# ControlBrick2_0.net
KiCad netlist of a schematic drawn in Altium Designer
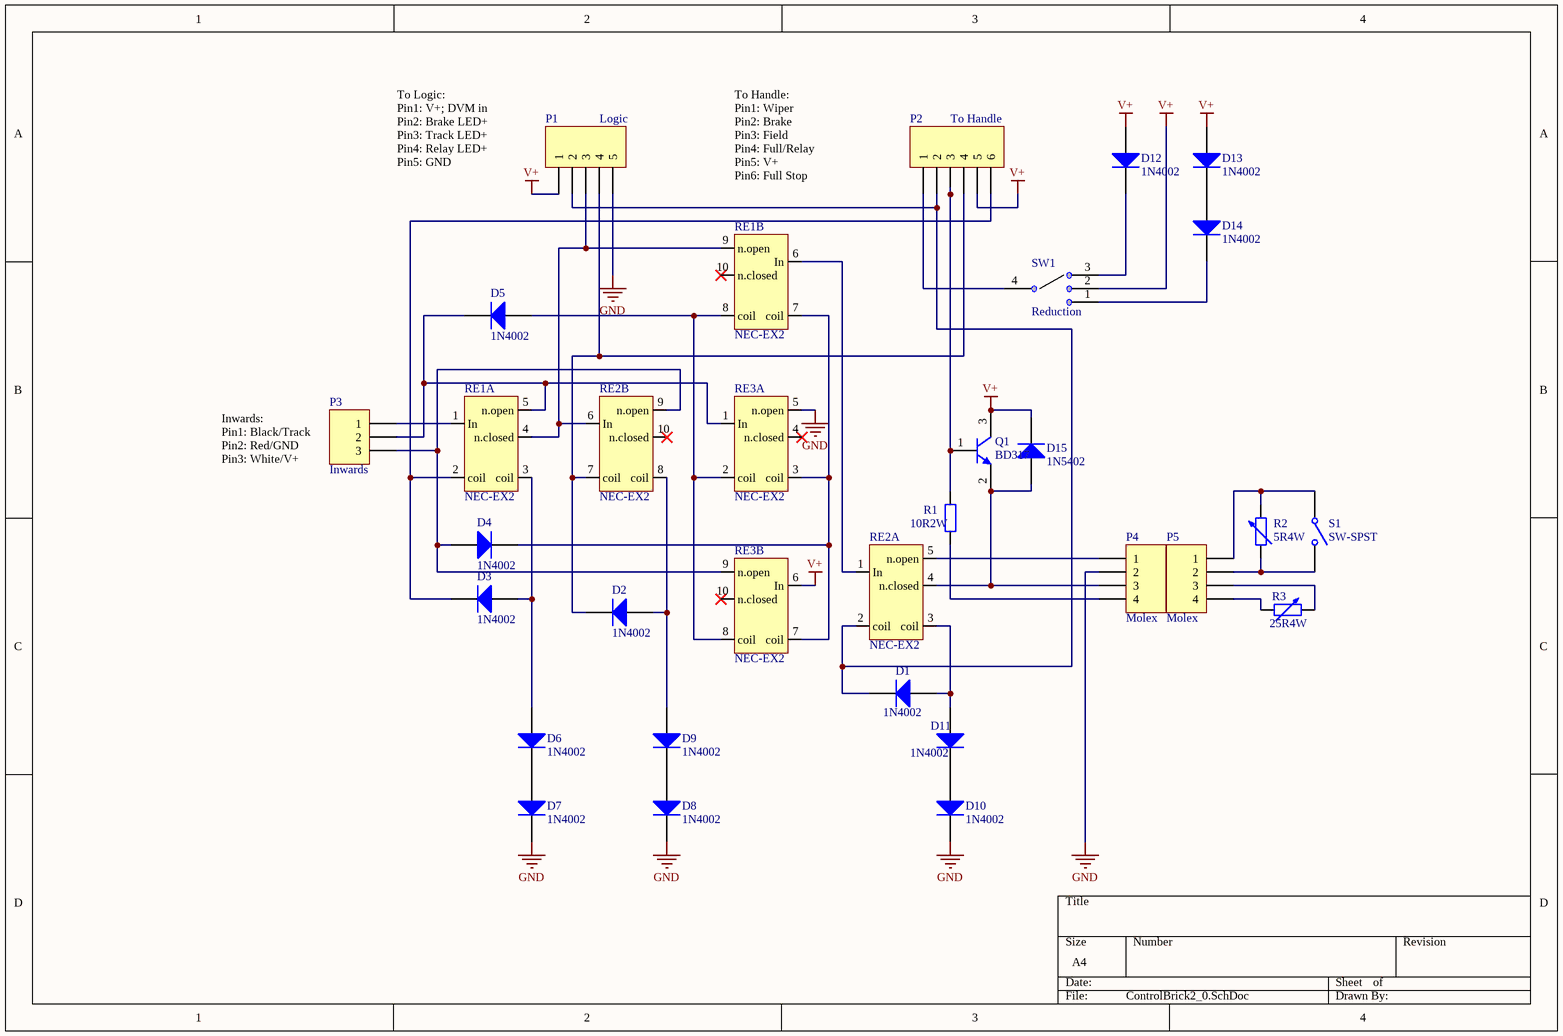
[diagram p0: ControlBrick2_0.SchDoc]

(export (version "E")
  (design (tool "Eeschema 10.0.6"))
  (components
    (comp (ref "D1")
      (value "1N4002")
      (footprint "StdDiode")
      (description "1 Amp General Purpose Rectifier")
      (fields (field (name "PUBLISHER") "Altium Limited"))
      (libsource (lib "Miscellaneous Devices") (part "Diode 1N4002"))
    )
    (comp (ref "D2")
      (value "1N4002")
      (footprint "StdDiode")
      (description "1 Amp General Purpose Rectifier")
      (fields (field (name "PUBLISHER") "Altium Limited"))
      (libsource (lib "Miscellaneous Devices") (part "Diode 1N4002"))
    )
    (comp (ref "D3")
      (value "1N4002")
      (footprint "StdDiode")
      (description "1 Amp General Purpose Rectifier")
      (fields (field (name "PUBLISHER") "Altium Limited"))
      (libsource (lib "Miscellaneous Devices") (part "Diode 1N4002"))
    )
    (comp (ref "D4")
      (value "1N4002")
      (footprint "StdDiode")
      (description "1 Amp General Purpose Rectifier")
      (fields (field (name "PUBLISHER") "Altium Limited"))
      (libsource (lib "Miscellaneous Devices") (part "Diode 1N4002"))
    )
    (comp (ref "D5")
      (value "1N4002")
      (footprint "StdDiode")
      (description "1 Amp General Purpose Rectifier")
      (fields (field (name "PUBLISHER") "Altium Limited"))
      (libsource (lib "Miscellaneous Devices") (part "Diode 1N4002"))
    )
    (comp (ref "D6")
      (value "1N4002")
      (footprint "StdDiode")
      (description "1 Amp General Purpose Rectifier")
      (fields (field (name "PUBLISHER") "Altium Limited"))
      (libsource (lib "Miscellaneous Devices") (part "Diode 1N4002"))
    )
    (comp (ref "D7")
      (value "1N4002")
      (footprint "StdDiode")
      (description "1 Amp General Purpose Rectifier")
      (fields (field (name "PUBLISHER") "Altium Limited"))
      (libsource (lib "Miscellaneous Devices") (part "Diode 1N4002"))
    )
    (comp (ref "D8")
      (value "1N4002")
      (footprint "StdDiode")
      (description "1 Amp General Purpose Rectifier")
      (fields (field (name "PUBLISHER") "Altium Limited"))
      (libsource (lib "Miscellaneous Devices") (part "Diode 1N4002"))
    )
    (comp (ref "D9")
      (value "1N4002")
      (footprint "StdDiode")
      (description "1 Amp General Purpose Rectifier")
      (fields (field (name "PUBLISHER") "Altium Limited"))
      (libsource (lib "Miscellaneous Devices") (part "Diode 1N4002"))
    )
    (comp (ref "D10")
      (value "1N4002")
      (footprint "StdDiode")
      (description "1 Amp General Purpose Rectifier")
      (fields (field (name "PUBLISHER") "Altium Limited"))
      (libsource (lib "Miscellaneous Devices") (part "Diode 1N4002"))
    )
    (comp (ref "D11")
      (value "1N4002")
      (footprint "StdDiode")
      (description "1 Amp General Purpose Rectifier")
      (fields (field (name "PUBLISHER") "Altium Limited"))
      (libsource (lib "Miscellaneous Devices") (part "Diode 1N4002"))
    )
    (comp (ref "D12")
      (value "1N4002")
      (footprint "StdDiode")
      (description "1 Amp General Purpose Rectifier")
      (fields (field (name "PUBLISHER") "Altium Limited"))
      (libsource (lib "Miscellaneous Devices") (part "Diode 1N4002"))
    )
    (comp (ref "D13")
      (value "1N4002")
      (footprint "StdDiode")
      (description "1 Amp General Purpose Rectifier")
      (fields (field (name "PUBLISHER") "Altium Limited"))
      (libsource (lib "Miscellaneous Devices") (part "Diode 1N4002"))
    )
    (comp (ref "D14")
      (value "1N4002")
      (footprint "StdDiode")
      (description "1 Amp General Purpose Rectifier")
      (fields (field (name "PUBLISHER") "Altium Limited"))
      (libsource (lib "Miscellaneous Devices") (part "Diode 1N4002"))
    )
    (comp (ref "D15")
      (value "1N5402")
      (footprint "BigDiode")
      (description "3 Amp General Purpose Rectifier")
      (fields (field (name "PUBLISHER") "Altium Limited"))
      (libsource (lib "Miscellaneous Devices") (part "Diode 1N5402"))
    )
    (comp (ref "P1")
      (value "Logic")
      (footprint "HDR1X5")
      (description "Header, 5-Pin")
      (fields (field (name "PUBLISHER") "Altium Limited"))
      (libsource (lib "Miscellaneous Connectors") (part "Header 5"))
    )
    (comp (ref "P2")
      (value "To Handle")
      (footprint "Interconnect")
      (description "Header, 6-Pin")
      (fields (field (name "PUBLISHER") "Altium Limited"))
      (libsource (lib "Miscellaneous Connectors") (part "Header 6"))
    )
    (comp (ref "P3")
      (value "Inwards")
      (footprint "Inwards")
      (description "Header, 3-Pin")
      (fields (field (name "PUBLISHER") "Altium Limited"))
      (libsource (lib "Miscellaneous Connectors") (part "Header 3"))
    )
    (comp (ref "P4")
      (value "Molex")
      (footprint "Molex_4x50.8")
      (description "Header, 4-Pin")
      (fields (field (name "PUBLISHER") "Altium Limited"))
      (libsource (lib "Miscellaneous Connectors") (part "Header 4"))
    )
    (comp (ref "P5")
      (value "Molex")
      (footprint "HDR1X4")
      (description "Header, 4-Pin")
      (fields (field (name "PUBLISHER") "Altium Limited"))
      (libsource (lib "") (part "Header 4_1"))
    )
    (comp (ref "Q1")
      (value "BD317")
      (footprint "TO-3")
      (description "NPN General Purpose Amplifier")
      (fields (field (name "PUBLISHER") "Altium Limited"))
      (libsource (lib "Miscellaneous Devices") (part "2N3904"))
    )
    (comp (ref "R1")
      (value "10R2W")
      (footprint "2Wres")
      (description "Resistor")
      (fields (field (name "PUBLISHER") "Altium Limited"))
      (libsource (lib "Miscellaneous Devices") (part "Res2"))
    )
    (comp (ref "R2")
      (value "5R4W")
      (footprint "AXIAL-0.6")
      (description "Variable Resistor")
      (fields (field (name "Comment") "Res Adj2") (field (name "PUBLISHER") "Altium Limited"))
      (libsource (lib "") (part "Res Adj2_1"))
    )
    (comp (ref "R3")
      (value "25R4W")
      (footprint "AXIAL-0.6")
      (description "Variable Resistor")
      (fields (field (name "Comment") "Res Adj2") (field (name "PUBLISHER") "Altium Limited"))
      (libsource (lib "Miscellaneous Devices") (part "Res Adj2"))
    )
    (comp (ref "RE1") (value "NEC-EX2") (footprint "NEC-EX2") (libsource (lib "") (part "Component_2_1")))
    (comp (ref "RE2")
      (value "NEC-EX2")
      (footprint "NEC-EX2")
      (libsource (lib "Schlib2") (part "Component_2"))
    )
    (comp (ref "RE3")
      (value "NEC-EX2")
      (footprint "NEC-EX2")
      (libsource (lib "Schlib2") (part "NEC-EX2-2U1S"))
    )
    (comp (ref "S1")
      (value "SW-SPST")
      (footprint "Switch SPST")
      (description "Single-Pole, Single-Throw Switch")
      (fields (field (name "PUBLISHER") "Altium Limited"))
      (libsource (lib "Miscellaneous Devices") (part "SW-SPST"))
    )
    (comp (ref "SW1") (value "Reduction") (footprint "Switch SP3T") (libsource (lib "Schlib1") (part "3Way")))
  )
  (nets
    (net (code "1") (name "GND") (class "Default")
      (node (ref "D10") (pin "2") (pinfunction "K_2") (pintype "passive"))
      (node (ref "D7") (pin "2") (pinfunction "K_2") (pintype "passive"))
      (node (ref "D8") (pin "2") (pinfunction "K_2") (pintype "passive"))
      (node (ref "P1") (pin "5") (pinfunction "5_5") (pintype "passive"))
      (node (ref "P4") (pin "2") (pinfunction "2_2") (pintype "passive"))
      (node (ref "RE3") (pin "5") (pinfunction "n.open_5") (pintype "passive"))
    )
    (net (code "2") (name "Net-(D1-A)") (class "Default")
      (node (ref "D1") (pin "1") (pinfunction "A_1") (pintype "passive"))
      (node (ref "D11") (pin "1") (pinfunction "A_1") (pintype "passive"))
      (node (ref "RE2") (pin "3") (pinfunction "coil_3") (pintype "passive"))
    )
    (net (code "3") (name "Net-(D1-K)") (class "Default")
      (node (ref "D1") (pin "2") (pinfunction "K_2") (pintype "passive"))
      (node (ref "P1") (pin "2") (pinfunction "2_2") (pintype "passive"))
      (node (ref "P2") (pin "2") (pinfunction "2_2") (pintype "passive"))
      (node (ref "RE2") (pin "2") (pinfunction "coil_2") (pintype "passive"))
    )
    (net (code "4") (name "Net-(D2-A)") (class "Default")
      (node (ref "D2") (pin "1") (pinfunction "A_1") (pintype "passive"))
      (node (ref "D9") (pin "1") (pinfunction "A_1") (pintype "passive"))
      (node (ref "RE2") (pin "8") (pinfunction "coil_8") (pintype "passive"))
    )
    (net (code "5") (name "Net-(D2-K)") (class "Default")
      (node (ref "D2") (pin "2") (pinfunction "K_2") (pintype "passive"))
      (node (ref "P1") (pin "4") (pinfunction "4_4") (pintype "passive"))
      (node (ref "P2") (pin "4") (pinfunction "4_4") (pintype "passive"))
      (node (ref "RE2") (pin "7") (pinfunction "coil_7") (pintype "passive"))
    )
    (net (code "6") (name "Net-(D3-A)") (class "Default")
      (node (ref "D3") (pin "1") (pinfunction "A_1") (pintype "passive"))
      (node (ref "D6") (pin "1") (pinfunction "A_1") (pintype "passive"))
      (node (ref "RE1") (pin "3") (pinfunction "coil_3") (pintype "passive"))
    )
    (net (code "7") (name "Net-(D3-K)") (class "Default")
      (node (ref "D3") (pin "2") (pinfunction "K_2") (pintype "passive"))
      (node (ref "P2") (pin "6") (pinfunction "6_6") (pintype "passive"))
      (node (ref "RE1") (pin "2") (pinfunction "coil_2") (pintype "passive"))
    )
    (net (code "8") (name "Net-(D4-A)") (class "Default")
      (node (ref "D4") (pin "1") (pinfunction "A_1") (pintype "passive"))
      (node (ref "P3") (pin "3") (pinfunction "3_3") (pintype "passive"))
      (node (ref "RE2") (pin "9") (pinfunction "n.open_9") (pintype "passive"))
      (node (ref "RE3") (pin "9") (pinfunction "n.open_9") (pintype "passive"))
    )
    (net (code "9") (name "Net-(D4-K)") (class "Default")
      (node (ref "D4") (pin "2") (pinfunction "K_2") (pintype "passive"))
      (node (ref "RE1") (pin "7") (pinfunction "coil_7") (pintype "passive"))
      (node (ref "RE3") (pin "3") (pinfunction "coil_3") (pintype "passive"))
      (node (ref "RE3") (pin "7") (pinfunction "coil_7") (pintype "passive"))
    )
    (net (code "10") (name "Net-(D5-A)") (class "Default")
      (node (ref "D5") (pin "1") (pinfunction "A_1") (pintype "passive"))
      (node (ref "RE1") (pin "8") (pinfunction "coil_8") (pintype "passive"))
      (node (ref "RE3") (pin "2") (pinfunction "coil_2") (pintype "passive"))
      (node (ref "RE3") (pin "8") (pinfunction "coil_8") (pintype "passive"))
    )
    (net (code "11") (name "Net-(D5-K)") (class "Default")
      (node (ref "D5") (pin "2") (pinfunction "K_2") (pintype "passive"))
      (node (ref "P3") (pin "2") (pinfunction "2_2") (pintype "passive"))
      (node (ref "RE1") (pin "5") (pinfunction "n.open_5") (pintype "passive"))
      (node (ref "RE3") (pin "1") (pinfunction "In_1") (pintype "passive"))
    )
    (net (code "12") (name "Net-(D6-K)") (class "Default")
      (node (ref "D6") (pin "2") (pinfunction "K_2") (pintype "passive"))
      (node (ref "D7") (pin "1") (pinfunction "A_1") (pintype "passive"))
    )
    (net (code "13") (name "Net-(D8-A)") (class "Default")
      (node (ref "D8") (pin "1") (pinfunction "A_1") (pintype "passive"))
      (node (ref "D9") (pin "2") (pinfunction "K_2") (pintype "passive"))
    )
    (net (code "14") (name "Net-(D10-A)") (class "Default")
      (node (ref "D10") (pin "1") (pinfunction "A_1") (pintype "passive"))
      (node (ref "D11") (pin "2") (pinfunction "K_2") (pintype "passive"))
    )
    (net (code "15") (name "Net-(D12-K)") (class "Default")
      (node (ref "D12") (pin "2") (pinfunction "K_2") (pintype "passive"))
      (node (ref "SW1") (pin "3") (pinfunction "3_3") (pintype "passive"))
    )
    (net (code "16") (name "Net-(D13-K)") (class "Default")
      (node (ref "D13") (pin "2") (pinfunction "K_2") (pintype "passive"))
      (node (ref "D14") (pin "1") (pinfunction "A_1") (pintype "passive"))
    )
    (net (code "17") (name "Net-(D14-K)") (class "Default")
      (node (ref "D14") (pin "2") (pinfunction "K_2") (pintype "passive"))
      (node (ref "SW1") (pin "1") (pinfunction "1_1") (pintype "passive"))
    )
    (net (code "18") (name "Net-(D15-A)") (class "Default")
      (node (ref "D15") (pin "1") (pinfunction "A_1") (pintype "passive"))
      (node (ref "P4") (pin "3") (pinfunction "3_3") (pintype "passive"))
      (node (ref "Q1") (pin "2") (pinfunction "E_2") (pintype "passive"))
      (node (ref "RE2") (pin "4") (pinfunction "n.closed_4") (pintype "passive"))
    )
    (net (code "19") (name "Net-(P2-Pad1)") (class "Default")
      (node (ref "P2") (pin "1") (pinfunction "1_1") (pintype "passive"))
      (node (ref "SW1") (pin "4") (pinfunction "4_4") (pintype "passive"))
    )
    (net (code "20") (name "Net-(P4-Pad4)") (class "Default")
      (node (ref "P4") (pin "4") (pinfunction "4_4") (pintype "passive"))
      (node (ref "R1") (pin "1") (pinfunction "1_1") (pintype "passive"))
    )
    (net (code "21") (name "Net-(P5-Pad3)") (class "Default")
      (node (ref "P5") (pin "3") (pinfunction "3_3") (pintype "passive"))
      (node (ref "R3") (pin "2") (pinfunction "2_2") (pintype "passive"))
    )
    (net (code "22") (name "Net-(P5-Pad4)") (class "Default")
      (node (ref "P5") (pin "4") (pinfunction "4_4") (pintype "passive"))
      (node (ref "R3") (pin "1") (pinfunction "1_1") (pintype "passive"))
    )
    (net (code "23") (name "Net-(Q1-B)") (class "Default")
      (node (ref "P2") (pin "3") (pinfunction "3_3") (pintype "passive"))
      (node (ref "Q1") (pin "1") (pinfunction "B_1") (pintype "passive"))
      (node (ref "R1") (pin "2") (pinfunction "2_2") (pintype "passive"))
    )
    (net (code "24") (name "Net-(RE1A-In)") (class "Default")
      (node (ref "P3") (pin "1") (pinfunction "1_1") (pintype "passive"))
      (node (ref "RE1") (pin "1") (pinfunction "In_1") (pintype "passive"))
    )
    (net (code "25") (name "Net-(RE1A-n.closed)") (class "Default")
      (node (ref "P1") (pin "3") (pinfunction "3_3") (pintype "passive"))
      (node (ref "RE1") (pin "4") (pinfunction "n.closed_4") (pintype "passive"))
      (node (ref "RE1") (pin "9") (pinfunction "n.open_9") (pintype "passive"))
      (node (ref "RE2") (pin "6") (pinfunction "In_6") (pintype "passive"))
    )
    (net (code "26") (name "Net-(RE1B-In)") (class "Default")
      (node (ref "RE1") (pin "6") (pinfunction "In_6") (pintype "passive"))
      (node (ref "RE2") (pin "1") (pinfunction "In_1") (pintype "passive"))
    )
    (net (code "27") (name "Net-(RE2A-n.open)") (class "Default")
      (node (ref "P4") (pin "1") (pinfunction "1_1") (pintype "passive"))
      (node (ref "RE2") (pin "5") (pinfunction "n.open_5") (pintype "passive"))
    )
    (net (code "28") (name "Net-(S1-COMMON)") (class "Default")
      (node (ref "P5") (pin "1") (pinfunction "1_1") (pintype "passive"))
      (node (ref "R2") (pin "2") (pinfunction "2_2") (pintype "passive"))
      (node (ref "S1") (pin "1") (pinfunction "COMMON_1") (pintype "passive"))
    )
    (net (code "29") (name "Net-(S1-NO)") (class "Default")
      (node (ref "P5") (pin "2") (pinfunction "2_2") (pintype "passive"))
      (node (ref "R2") (pin "1") (pinfunction "1_1") (pintype "passive"))
      (node (ref "S1") (pin "2") (pinfunction "NO_2") (pintype "passive"))
    )
    (net (code "30") (name "V+") (class "Default")
      (node (ref "D12") (pin "1") (pinfunction "A_1") (pintype "passive"))
      (node (ref "D13") (pin "1") (pinfunction "A_1") (pintype "passive"))
      (node (ref "D15") (pin "2") (pinfunction "K_2") (pintype "passive"))
      (node (ref "P1") (pin "1") (pinfunction "1_1") (pintype "passive"))
      (node (ref "P2") (pin "5") (pinfunction "5_5") (pintype "passive"))
      (node (ref "Q1") (pin "3") (pinfunction "C_3") (pintype "passive"))
      (node (ref "RE3") (pin "6") (pinfunction "In_6") (pintype "passive"))
      (node (ref "SW1") (pin "2") (pinfunction "2_2") (pintype "passive"))
    )
    (net (code "31") (name "unconnected-(RE1B-n.closed-Pad10)") (class "Default")
      (node (ref "RE1") (pin "10") (pinfunction "n.closed_10") (pintype "passive+no_connect"))
    )
    (net (code "32") (name "unconnected-(RE2B-n.closed-Pad10)") (class "Default")
      (node (ref "RE2") (pin "10") (pinfunction "n.closed_10") (pintype "passive+no_connect"))
    )
    (net (code "33") (name "unconnected-(RE3A-n.closed-Pad4)") (class "Default")
      (node (ref "RE3") (pin "4") (pinfunction "n.closed_4") (pintype "passive+no_connect"))
    )
    (net (code "34") (name "unconnected-(RE3B-n.closed-Pad10)") (class "Default")
      (node (ref "RE3") (pin "10") (pinfunction "n.closed_10") (pintype "passive+no_connect"))
    )
  )
)
